# Flipdot_Control.net
KiCad netlist of a schematic drawn in EAGLE
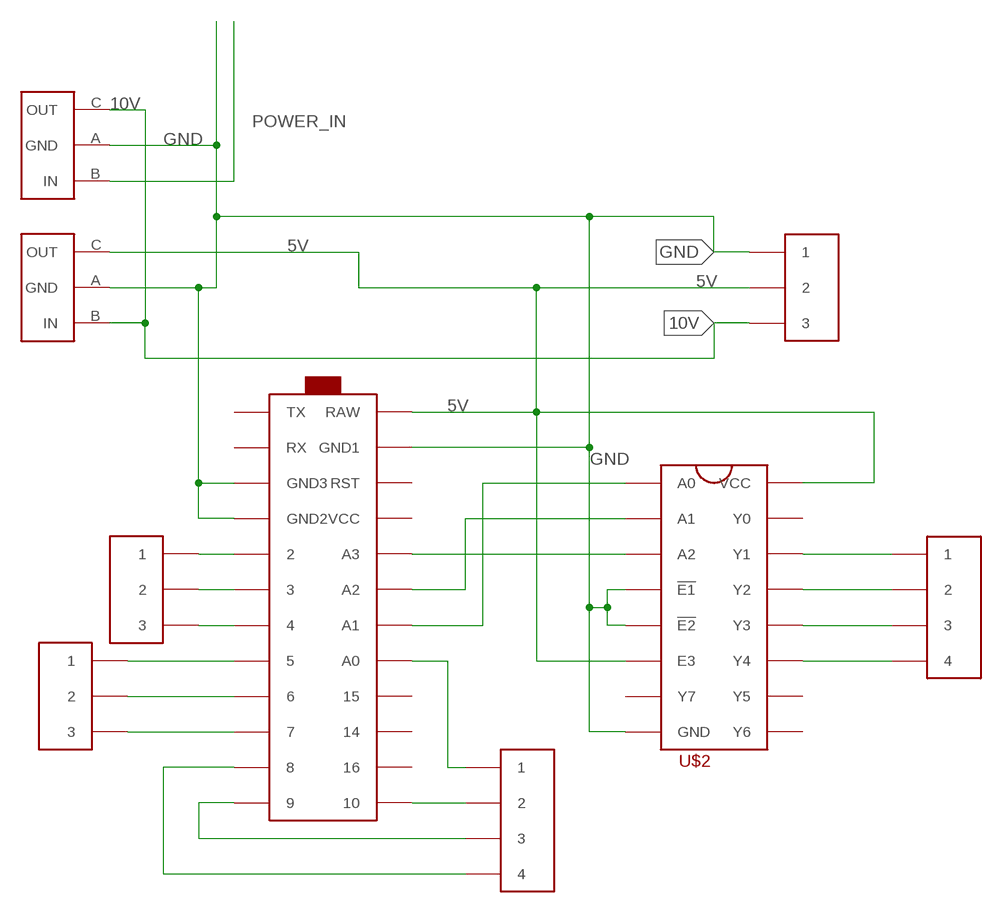
[diagram p0: schematic, sheet 1]

(export (version "E")
  (design (tool "Eeschema 10.0.6"))
  (components
    (comp (ref "U$1")
      (value "MCU")
      (footprint "eagle-import:SPARKFUN_PRO_MICRO")
      (libsource (lib "eagle-import") (part "MCU"))
    )
    (comp (ref "U$2")
      (value "74HC238")
      (footprint "eagle-import:DIL16")
      (libsource (lib "eagle-import") (part "74HC238"))
    )
    (comp (ref "U$3")
      (value "4_PIN")
      (footprint "eagle-import:4_PIN")
      (libsource (lib "eagle-import") (part "4_PIN"))
    )
    (comp (ref "U$4")
      (value "4_PIN")
      (footprint "eagle-import:4_PIN")
      (libsource (lib "eagle-import") (part "4_PIN"))
    )
    (comp (ref "U$5")
      (value "3_PIN")
      (footprint "eagle-import:3_PIN")
      (libsource (lib "eagle-import") (part "3_PIN"))
    )
    (comp (ref "U$6")
      (value "3_PIN")
      (footprint "eagle-import:3_PIN")
      (libsource (lib "eagle-import") (part "3_PIN"))
    )
    (comp (ref "U$7")
      (value "3_PIN")
      (footprint "eagle-import:3_PIN")
      (libsource (lib "eagle-import") (part "3_PIN"))
    )
    (comp (ref "U$8")
      (value "POWER")
      (footprint "eagle-import:POWER")
      (libsource (lib "eagle-import") (part "POWER"))
    )
    (comp (ref "U$9")
      (value "POWER")
      (footprint "eagle-import:POWER")
      (libsource (lib "eagle-import") (part "POWER"))
    )
  )
  (nets
    (net (code "1") (name "/5V") (class "Default")
      (node (ref "U$1") (pin "24") (pinfunction "RAW_24") (pintype "bidirectional"))
      (node (ref "U$2") (pin "16") (pinfunction "VCC_16") (pintype "bidirectional"))
      (node (ref "U$2") (pin "6") (pinfunction "E3_6") (pintype "bidirectional"))
      (node (ref "U$7") (pin "P$2") (pinfunction "2_P$2") (pintype "bidirectional"))
      (node (ref "U$8") (pin "C") (pinfunction "OUT_C") (pintype "bidirectional"))
    )
    (net (code "2") (name "/POWER_IN") (class "Default")
      (node (ref "U$9") (pin "B") (pinfunction "IN_B") (pintype "bidirectional"))
    )
    (net (code "3") (name "10V") (class "Default")
      (node (ref "U$7") (pin "P$3") (pinfunction "3_P$3") (pintype "bidirectional"))
      (node (ref "U$8") (pin "B") (pinfunction "IN_B") (pintype "bidirectional"))
      (node (ref "U$9") (pin "C") (pinfunction "OUT_C") (pintype "bidirectional"))
    )
    (net (code "4") (name "GND") (class "Default")
      (node (ref "U$1") (pin "23") (pinfunction "GND1_23") (pintype "bidirectional"))
      (node (ref "U$1") (pin "3") (pinfunction "GND3_3") (pintype "bidirectional"))
      (node (ref "U$1") (pin "4") (pinfunction "GND2_4") (pintype "bidirectional"))
      (node (ref "U$2") (pin "4") (pinfunction "~{E1}_4") (pintype "bidirectional"))
      (node (ref "U$2") (pin "5") (pinfunction "~{E2}_5") (pintype "bidirectional"))
      (node (ref "U$2") (pin "8") (pinfunction "GND_8") (pintype "bidirectional"))
      (node (ref "U$7") (pin "P$1") (pinfunction "1_P$1") (pintype "bidirectional"))
      (node (ref "U$8") (pin "A") (pinfunction "GND_A") (pintype "bidirectional"))
      (node (ref "U$9") (pin "A") (pinfunction "GND_A") (pintype "bidirectional"))
    )
    (net (code "5") (name "Net-(U$1-2)") (class "Default")
      (node (ref "U$1") (pin "5") (pinfunction "2_5") (pintype "bidirectional"))
      (node (ref "U$5") (pin "P$1") (pinfunction "1_P$1") (pintype "bidirectional"))
    )
    (net (code "6") (name "Net-(U$1-3)") (class "Default")
      (node (ref "U$1") (pin "6") (pinfunction "3_6") (pintype "bidirectional"))
      (node (ref "U$5") (pin "P$2") (pinfunction "2_P$2") (pintype "bidirectional"))
    )
    (net (code "7") (name "Net-(U$1-4)") (class "Default")
      (node (ref "U$1") (pin "7") (pinfunction "4_7") (pintype "bidirectional"))
      (node (ref "U$5") (pin "P$3") (pinfunction "3_P$3") (pintype "bidirectional"))
    )
    (net (code "8") (name "Net-(U$1-5)") (class "Default")
      (node (ref "U$1") (pin "8") (pinfunction "5_8") (pintype "bidirectional"))
      (node (ref "U$6") (pin "P$1") (pinfunction "1_P$1") (pintype "bidirectional"))
    )
    (net (code "9") (name "Net-(U$1-6)") (class "Default")
      (node (ref "U$1") (pin "9") (pinfunction "6_9") (pintype "bidirectional"))
      (node (ref "U$6") (pin "P$2") (pinfunction "2_P$2") (pintype "bidirectional"))
    )
    (net (code "10") (name "Net-(U$1-7)") (class "Default")
      (node (ref "U$1") (pin "10") (pinfunction "7_10") (pintype "bidirectional"))
      (node (ref "U$6") (pin "P$3") (pinfunction "3_P$3") (pintype "bidirectional"))
    )
    (net (code "11") (name "Net-(U$1-8)") (class "Default")
      (node (ref "U$1") (pin "11") (pinfunction "8_11") (pintype "bidirectional"))
      (node (ref "U$4") (pin "P$4") (pinfunction "4_P$4") (pintype "bidirectional"))
    )
    (net (code "12") (name "Net-(U$1-9)") (class "Default")
      (node (ref "U$1") (pin "12") (pinfunction "9_12") (pintype "bidirectional"))
      (node (ref "U$4") (pin "P$3") (pinfunction "3_P$3") (pintype "bidirectional"))
    )
    (net (code "13") (name "Net-(U$1-10)") (class "Default")
      (node (ref "U$1") (pin "13") (pinfunction "10_13") (pintype "bidirectional"))
      (node (ref "U$4") (pin "P$2") (pinfunction "2_P$2") (pintype "bidirectional"))
    )
    (net (code "14") (name "Net-(U$1-A0)") (class "Default")
      (node (ref "U$1") (pin "17") (pinfunction "A0_17") (pintype "bidirectional"))
      (node (ref "U$4") (pin "P$1") (pinfunction "1_P$1") (pintype "bidirectional"))
    )
    (net (code "15") (name "Net-(U$1-A1)") (class "Default")
      (node (ref "U$1") (pin "18") (pinfunction "A1_18") (pintype "bidirectional"))
      (node (ref "U$2") (pin "1") (pinfunction "A0_1") (pintype "bidirectional"))
    )
    (net (code "16") (name "Net-(U$1-A2)") (class "Default")
      (node (ref "U$1") (pin "19") (pinfunction "A2_19") (pintype "bidirectional"))
      (node (ref "U$2") (pin "2") (pinfunction "A1_2") (pintype "bidirectional"))
    )
    (net (code "17") (name "Net-(U$1-A3)") (class "Default")
      (node (ref "U$1") (pin "20") (pinfunction "A3_20") (pintype "bidirectional"))
      (node (ref "U$2") (pin "3") (pinfunction "A2_3") (pintype "bidirectional"))
    )
    (net (code "18") (name "Net-(U$2-Y1)") (class "Default")
      (node (ref "U$2") (pin "14") (pinfunction "Y1_14") (pintype "bidirectional"))
      (node (ref "U$3") (pin "P$1") (pinfunction "1_P$1") (pintype "bidirectional"))
    )
    (net (code "19") (name "Net-(U$2-Y2)") (class "Default")
      (node (ref "U$2") (pin "13") (pinfunction "Y2_13") (pintype "bidirectional"))
      (node (ref "U$3") (pin "P$2") (pinfunction "2_P$2") (pintype "bidirectional"))
    )
    (net (code "20") (name "Net-(U$2-Y3)") (class "Default")
      (node (ref "U$2") (pin "12") (pinfunction "Y3_12") (pintype "bidirectional"))
      (node (ref "U$3") (pin "P$3") (pinfunction "3_P$3") (pintype "bidirectional"))
    )
    (net (code "21") (name "Net-(U$2-Y4)") (class "Default")
      (node (ref "U$2") (pin "11") (pinfunction "Y4_11") (pintype "bidirectional"))
      (node (ref "U$3") (pin "P$4") (pinfunction "4_P$4") (pintype "bidirectional"))
    )
    (net (code "22") (name "unconnected-(U$1-14-Pad15)") (class "Default")
      (node (ref "U$1") (pin "15") (pinfunction "14_15") (pintype "bidirectional"))
    )
    (net (code "23") (name "unconnected-(U$1-15-Pad16)") (class "Default")
      (node (ref "U$1") (pin "16") (pinfunction "15_16") (pintype "bidirectional"))
    )
    (net (code "24") (name "unconnected-(U$1-16-Pad14)") (class "Default")
      (node (ref "U$1") (pin "14") (pinfunction "16_14") (pintype "bidirectional"))
    )
    (net (code "25") (name "unconnected-(U$1-RST-Pad22)") (class "Default")
      (node (ref "U$1") (pin "22") (pinfunction "RST_22") (pintype "bidirectional"))
    )
    (net (code "26") (name "unconnected-(U$1-RX-Pad2)") (class "Default")
      (node (ref "U$1") (pin "2") (pinfunction "RX_2") (pintype "bidirectional"))
    )
    (net (code "27") (name "unconnected-(U$1-TX-Pad1)") (class "Default")
      (node (ref "U$1") (pin "1") (pinfunction "TX_1") (pintype "bidirectional"))
    )
    (net (code "28") (name "unconnected-(U$1-VCC-Pad21)") (class "Default")
      (node (ref "U$1") (pin "21") (pinfunction "VCC_21") (pintype "bidirectional"))
    )
    (net (code "29") (name "unconnected-(U$2-Y0-Pad15)") (class "Default")
      (node (ref "U$2") (pin "15") (pinfunction "Y0_15") (pintype "bidirectional"))
    )
    (net (code "30") (name "unconnected-(U$2-Y5-Pad10)") (class "Default")
      (node (ref "U$2") (pin "10") (pinfunction "Y5_10") (pintype "bidirectional"))
    )
    (net (code "31") (name "unconnected-(U$2-Y6-Pad9)") (class "Default")
      (node (ref "U$2") (pin "9") (pinfunction "Y6_9") (pintype "bidirectional"))
    )
    (net (code "32") (name "unconnected-(U$2-Y7-Pad7)") (class "Default")
      (node (ref "U$2") (pin "7") (pinfunction "Y7_7") (pintype "bidirectional"))
    )
  )
)
